# R_Phase_Sense_Signal_Isolation.net
KiCad netlist of a schematic drawn in Altium Designer
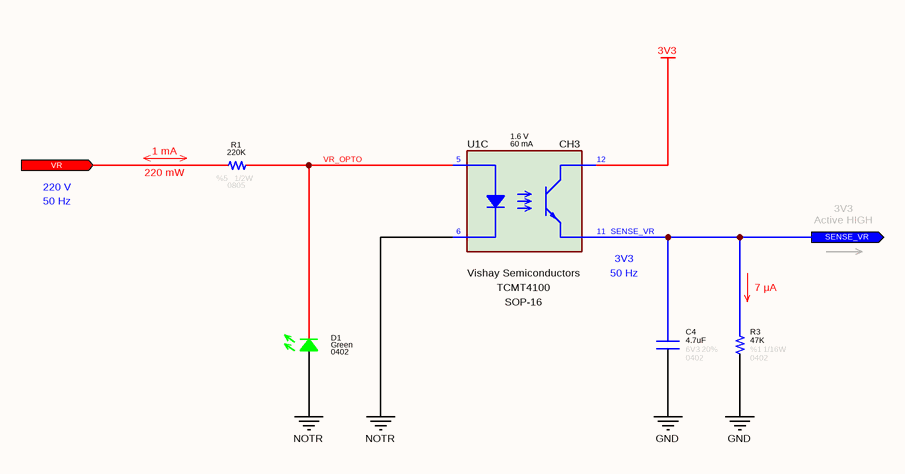
[diagram p0: R Phase Sense Signal Isolation.SchDoc]

(export (version "E")
  (design (tool "Eeschema 10.0.6"))
  (components
    (comp (ref "C4")
      (value "4.7uF")
      (footprint "CAPACITOR_0402")
      (description "Multilayer Ceramic Capacitors - SMD - 6V3 4.7uF X5R 0402 20%")
      (fields
        (field (name "MANUFACTURER PART NUMBER") "C0402C475M9PACTU")
        (field (name "TOLERANCE") "20%")
        (field (name "CASE") "0402")
        (field (name "VOLTAGE") "6V3")
        (field (name "Comment") "Capacitor - 4.7uF [0402] (Ceramic)")
      )
      (libsource (lib "Akkoyun") (part "Capacitor - 4.7uF [0402-6V3]"))
    )
    (comp (ref "D1")
      (value "SMD LED (Green)")
      (footprint "LED_0402")
      (description "Standard LEDs - SMD MINI-MOLD ULTRA COMPACT GREEN")
      (fields
        (field (name "MANUFACTURER PART NUMBER") "SML-P12MTT86R")
        (field (name "CASE") "0402")
        (field (name "COLOR") "Green")
      )
      (libsource (lib "Akkoyun") (part "Diode - LED (0402-Green)"))
    )
    (comp (ref "R1")
      (value "220K")
      (footprint "RESISTOR_0805")
      (description "Thick Film Resistors - SMD 1/2 W 220 KOhm 5%")
      (fields
        (field (name "MANUFACTURER PART NUMBER") "CRCW0805220KJNEAHP")
        (field (name "CASE") "0805")
        (field (name "TOLERANCE") "%5")
        (field (name "POWER") "1/2W")
        (field (name "Comment") "220K - 0805 - %5 - 1/16W")
      )
      (libsource (lib "Akkoyun") (part "Resistor - 220K [0805]"))
    )
    (comp (ref "R3")
      (value "47K")
      (footprint "RESISTOR_0402")
      (description "Thick Film Resistors - SMD 1/16 W 47 KOhm 1%")
      (fields
        (field (name "MANUFACTURER PART NUMBER") "CRCW040247K0FKED")
        (field (name "TOLERANCE") "%1")
        (field (name "CASE") "0402")
        (field (name "POWER") "1/16W")
        (field (name "Comment") "47K - 0402 - %1 - 1/16W")
      )
      (libsource (lib "Akkoyun") (part "Resistor - 47K [0402]"))
    )
    (comp (ref "U1")
      (value "TCMT4100")
      (footprint "SO-16")
      (description "OptpCoupler 4CH 16 Pin (SOP16)")
      (fields
        (field (name "IF - FORWARD CURRENT") "60 mA")
        (field (name "VF - FORWARD VOLTAGE") "1.6 V")
        (field (name "MANUFACTURER NAME") "Vishay Semiconductors")
        (field (name "MANUFACTURER PART NUMBER") "TCMT4100")
        (field (name "CASE") "SOP-16")
      )
      (libsource (lib "Akkoyun") (part "IC - TCMT4100"))
    )
  )
  (nets
    (net (code "1") (name "/SENSE_VR") (class "Default")
      (node (ref "C4") (pin "2") (pinfunction "2_2") (pintype "passive"))
      (node (ref "R3") (pin "2") (pinfunction "2_2") (pintype "passive"))
      (node (ref "U1") (pin "11") (pinfunction "Emiter_CH3_11") (pintype "open_emitter"))
    )
    (net (code "2") (name "/VR") (class "Default")
      (node (ref "R1") (pin "2") (pinfunction "2_2") (pintype "passive"))
    )
    (net (code "3") (name "/VR_OPTO") (class "Default")
      (node (ref "D1") (pin "1") (pinfunction "1_1") (pintype "passive"))
      (node (ref "R1") (pin "1") (pinfunction "1_1") (pintype "passive"))
      (node (ref "U1") (pin "5") (pinfunction "Anode_CH3_5") (pintype "passive"))
    )
    (net (code "4") (name "3V3") (class "Default")
      (node (ref "U1") (pin "12") (pinfunction "Collector_CH3_12") (pintype "passive"))
    )
    (net (code "5") (name "GND") (class "Default")
      (node (ref "C4") (pin "1") (pinfunction "1_1") (pintype "passive"))
      (node (ref "R3") (pin "1") (pinfunction "1_1") (pintype "passive"))
    )
    (net (code "6") (name "NOTR") (class "Default")
      (node (ref "D1") (pin "2") (pinfunction "2_2") (pintype "passive"))
      (node (ref "U1") (pin "6") (pinfunction "Cathode_CH3_6") (pintype "passive"))
    )
  )
)
